# SCH_Clock_Led.net
KiCad netlist of a schematic drawn in Altium Designer
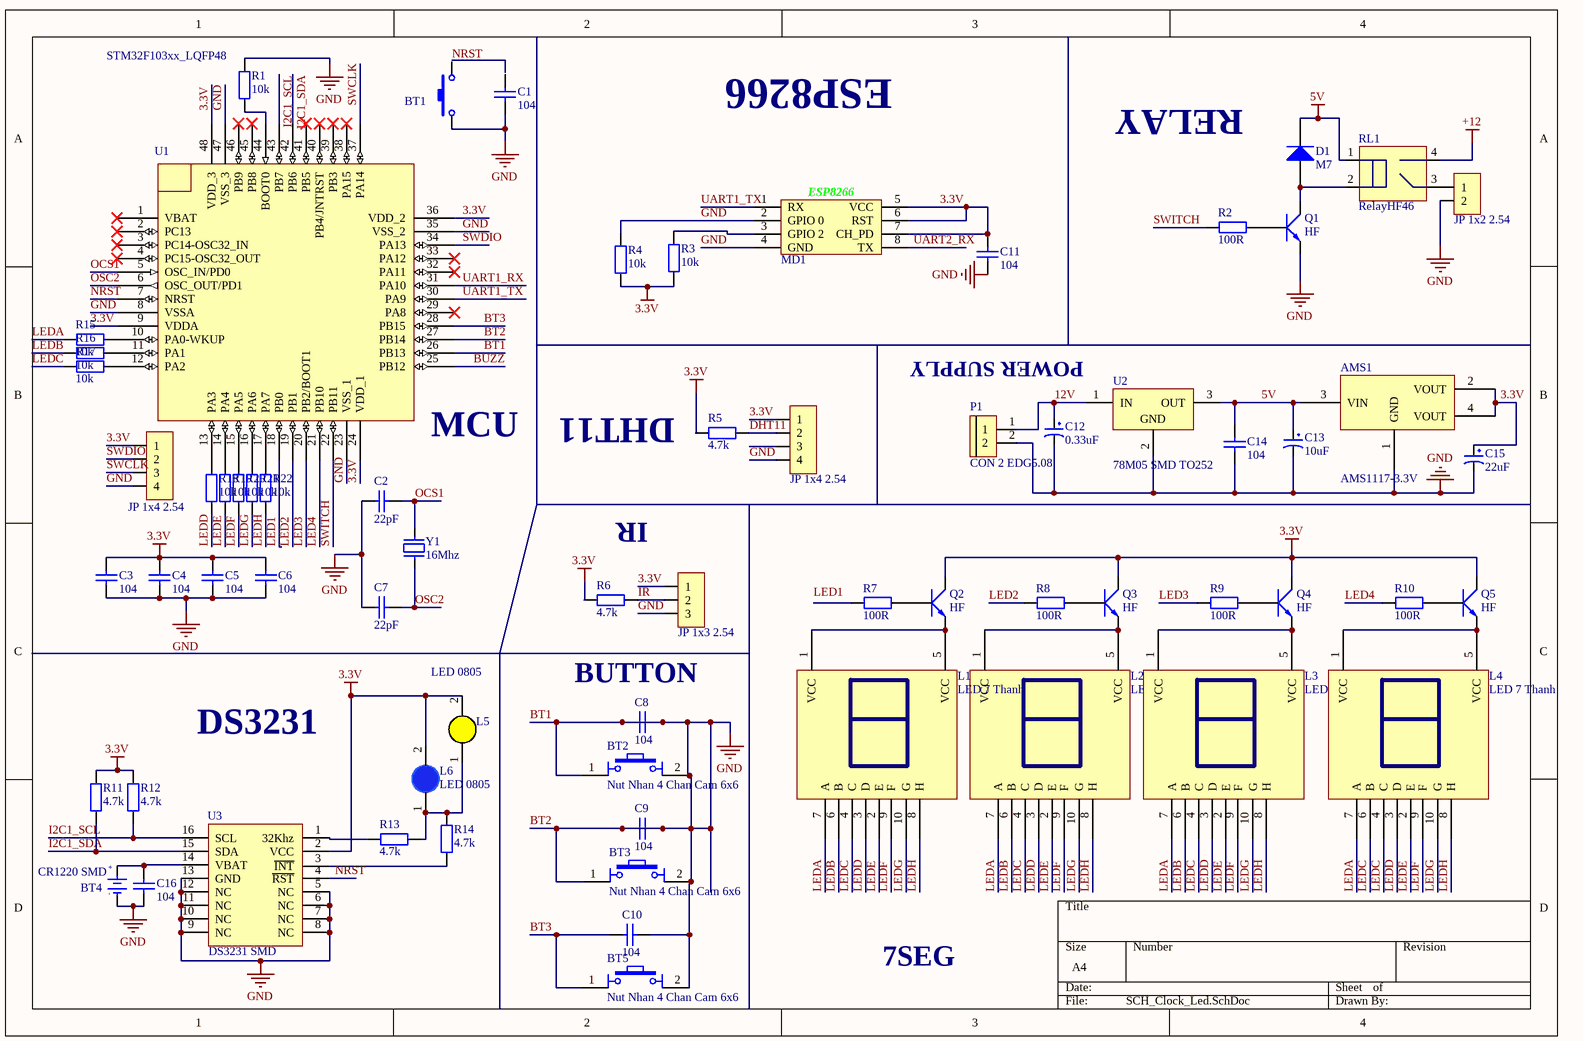
[diagram p0: SCH_Clock_Led.SchDoc]

(export (version "E")
  (design (tool "Eeschema 10.0.6"))
  (components
    (comp (ref "AMS1")
      (value "AMS1117-3.3V")
      (footprint "SOT223")
      (description "Dán")
      (libsource (lib "Altium_Lib_by_KhueNguyenCreator") (part "AMS1117 SMD"))
    )
    (comp (ref "BT1")
      (value "Nut Nhan 2 Chan SMD 3x6x2.5")
      (footprint "Nut Nhan 2 Chan SMD 3x6x2.5")
      (libsource (lib "Altium_Lib_by_KhueNguyenCreator") (part "Nut Nhan 2 Chan SMD 3x6x2.5"))
    )
    (comp (ref "BT2")
      (value "Nut Nhan 4 Chan Cam 6x6")
      (footprint "Nut Nhan 4 Chan Cam 6x6")
      (description "Nut Nhan 4 Chan 6x6mm")
      (libsource (lib "Altium_Lib_by_KhueNguyenCreator") (part "Nut Nhan 4 Chan Cam 6x6"))
    )
    (comp (ref "BT3")
      (value "Nut Nhan 4 Chan Cam 6x6")
      (footprint "Nut Nhan 4 Chan Cam 6x6")
      (description "Nut Nhan 4 Chan 6x6mm")
      (libsource (lib "Altium_Lib_by_KhueNguyenCreator") (part "Nut Nhan 4 Chan Cam 6x6"))
    )
    (comp (ref "BT4")
      (value "CR1220 SMD")
      (footprint "DE PIN CR1220")
      (libsource (lib "Altium_Lib_by_KhueNguyenCreator") (part "De pin CR1220 SMD"))
    )
    (comp (ref "BT5")
      (value "Nut Nhan 4 Chan Cam 6x6")
      (footprint "Nut Nhan 4 Chan Cam 6x6")
      (description "Nut Nhan 4 Chan 6x6mm")
      (libsource (lib "Altium_Lib_by_KhueNguyenCreator") (part "Nut Nhan 4 Chan Cam 6x6"))
    )
    (comp (ref "C1")
      (value "104")
      (footprint "tu 0805")
      (description "Dán")
      (libsource (lib "Altium_Lib_by_KhueNguyenCreator") (part "Tu 0805 104 50V 10%"))
    )
    (comp (ref "C2")
      (value "22pF")
      (footprint "tu 0805")
      (description "Dán")
      (libsource (lib "Altium_Lib_by_KhueNguyenCreator") (part "Tu 0805 22pF 50V 10%"))
    )
    (comp (ref "C3")
      (value "104")
      (footprint "tu 0805")
      (description "Dán")
      (libsource (lib "Altium_Lib_by_KhueNguyenCreator") (part "Tu 0805 104 50V 10%"))
    )
    (comp (ref "C4")
      (value "104")
      (footprint "tu 0805")
      (description "Dán")
      (libsource (lib "Altium_Lib_by_KhueNguyenCreator") (part "Tu 0805 104 50V 10%"))
    )
    (comp (ref "C5")
      (value "104")
      (footprint "tu 0805")
      (description "Dán")
      (libsource (lib "Altium_Lib_by_KhueNguyenCreator") (part "Tu 0805 104 50V 10%"))
    )
    (comp (ref "C6")
      (value "104")
      (footprint "tu 0805")
      (description "Dán")
      (libsource (lib "Altium_Lib_by_KhueNguyenCreator") (part "Tu 0805 104 50V 10%"))
    )
    (comp (ref "C7")
      (value "22pF")
      (footprint "tu 0805")
      (description "Dán")
      (libsource (lib "Altium_Lib_by_KhueNguyenCreator") (part "Tu 0805 22pF 50V 10%"))
    )
    (comp (ref "C8")
      (value "104")
      (footprint "tu 0805")
      (description "Dán")
      (libsource (lib "Altium_Lib_by_KhueNguyenCreator") (part "Tu 0805 104 50V 10%"))
    )
    (comp (ref "C9")
      (value "104")
      (footprint "tu 0805")
      (description "Dán")
      (libsource (lib "Altium_Lib_by_KhueNguyenCreator") (part "Tu 0805 104 50V 10%"))
    )
    (comp (ref "C10")
      (value "104")
      (footprint "tu 0805")
      (description "Dán")
      (libsource (lib "Altium_Lib_by_KhueNguyenCreator") (part "Tu 0805 104 50V 10%"))
    )
    (comp (ref "C11")
      (value "104")
      (footprint "tu 0805")
      (description "Dán")
      (libsource (lib "Altium_Lib_by_KhueNguyenCreator") (part "Tu 0805 104 50V 10%"))
    )
    (comp (ref "C12")
      (value "0.33uF")
      (footprint "tu hoa 5mm")
      (description "Cắm")
      (libsource (lib "Altium_Lib_by_KhueNguyenCreator") (part "Tu Hoa 0.33uF 50V 5x11"))
    )
    (comp (ref "C13")
      (value "10uF")
      (footprint "tu hoa 13mm")
      (description "Cắm")
      (libsource (lib "Altium_Lib_by_KhueNguyenCreator") (part "Tu Hoa 10uF 450V 13x20"))
    )
    (comp (ref "C14")
      (value "104")
      (footprint "tu 0805")
      (description "Dán")
      (libsource (lib "Altium_Lib_by_KhueNguyenCreator") (part "Tu 0805 104 50V 10%"))
    )
    (comp (ref "C15")
      (value "22uF")
      (footprint "tu hoa 5mm")
      (description "Cắm")
      (libsource (lib "Altium_Lib_by_KhueNguyenCreator") (part "Tu Hoa 22uF 35V 5x11"))
    )
    (comp (ref "C16")
      (value "104")
      (footprint "tu 0805")
      (description "Dán")
      (libsource (lib "Altium_Lib_by_KhueNguyenCreator") (part "Tu 0805 104 50V 10%"))
    )
    (comp (ref "D1")
      (value "M7")
      (footprint "DIODE SMA")
      (description "Dán")
      (libsource (lib "Altium_Lib_by_KhueNguyenCreator") (part "Diode M7 ( 4007 )"))
    )
    (comp (ref "JP1")
      (value "JP 1x4 2.54")
      (footprint "JP 1x4 DT")
      (description "Cắm")
      (libsource (lib "Altium_Lib_by_KhueNguyenCreator") (part "JP 1x4 2.54 Duc Thang"))
    )
    (comp (ref "JP2")
      (value "JP 1x4 2.54")
      (footprint "JP 1x4 DT")
      (description "Cắm")
      (libsource (lib "Altium_Lib_by_KhueNguyenCreator") (part "JP 1x4 2.54 Duc Thang"))
    )
    (comp (ref "JP3")
      (value "JP 1x3 2.54")
      (footprint "JP 1x3 CT")
      (description "Cắm")
      (libsource (lib "Altium_Lib_by_KhueNguyenCreator") (part "JP 1x3 2.54 Cai Thang"))
    )
    (comp (ref "JP4")
      (value "JP 1x2 2.54")
      (footprint "JP 1x2 DT")
      (description "Cắm")
      (libsource (lib "Altium_Lib_by_KhueNguyenCreator") (part "JP 1x2 2.54 Duc Thang"))
    )
    (comp (ref "L1")
      (value "LED 7 Thanh")
      (description "Dán")
      (libsource (lib "Altium_Lib_by_KhueNguyenCreator") (part "LED 7x1 2.3inch Anot"))
    )
    (comp (ref "L2")
      (value "LED 7 Thanh")
      (description "Dán")
      (libsource (lib "Altium_Lib_by_KhueNguyenCreator") (part "LED 7x1 2.3inch Anot"))
    )
    (comp (ref "L3")
      (value "LED 7 Thanh")
      (description "Dán")
      (libsource (lib "Altium_Lib_by_KhueNguyenCreator") (part "LED 7x1 2.3inch Anot"))
    )
    (comp (ref "L4")
      (value "LED 7 Thanh")
      (description "Dán")
      (libsource (lib "Altium_Lib_by_KhueNguyenCreator") (part "LED 7x1 2.3inch Anot"))
    )
    (comp (ref "L5")
      (value "LED 0805")
      (footprint "LED-1206-Yellow")
      (description "Dán")
      (libsource (lib "Altium_Lib_by_KhueNguyenCreator") (part "LED 1206 Vang"))
    )
    (comp (ref "L6")
      (value "LED 0805")
      (footprint "LED-0805-Blue")
      (description "Dán")
      (libsource (lib "Altium_Lib_by_KhueNguyenCreator") (part "LED 0805 Xanh Duong"))
    )
    (comp (ref "MD1")
      (value "ESP8266 Module")
      (footprint "ESP2866 Module")
      (libsource (lib "Altium_Lib_by_KhueNguyenCreator") (part "ESP8266 Module"))
    )
    (comp (ref "P1")
      (value "CON 2 EDG5.08")
      (footprint "CON 2 2EDG5.08")
      (description "Cắm")
      (libsource (lib "Altium_Lib_by_KhueNguyenCreator") (part "CON 2 EDG5.08"))
    )
    (comp (ref "Q1")
      (value "HF")
      (footprint "SOT23")
      (description "NPN transistor")
      (libsource (lib "Altium_Lib_by_KhueNguyenCreator") (part "C1815 HF SMD"))
    )
    (comp (ref "Q2")
      (value "HF")
      (footprint "SOT23")
      (description "NPN transistor")
      (libsource (lib "Altium_Lib_by_KhueNguyenCreator") (part "C1815 HF SMD"))
    )
    (comp (ref "Q3")
      (value "HF")
      (footprint "SOT23")
      (description "NPN transistor")
      (libsource (lib "Altium_Lib_by_KhueNguyenCreator") (part "C1815 HF SMD"))
    )
    (comp (ref "Q4")
      (value "HF")
      (footprint "SOT23")
      (description "NPN transistor")
      (libsource (lib "Altium_Lib_by_KhueNguyenCreator") (part "C1815 HF SMD"))
    )
    (comp (ref "Q5")
      (value "HF")
      (footprint "SOT23")
      (description "NPN transistor")
      (libsource (lib "Altium_Lib_by_KhueNguyenCreator") (part "C1815 HF SMD"))
    )
    (comp (ref "R1")
      (value "10k")
      (footprint "tro smd 0805")
      (description "Dán")
      (libsource (lib "Altium_Lib_by_KhueNguyenCreator") (part "Tro 0805 5% 10k"))
    )
    (comp (ref "R2")
      (value "100R")
      (footprint "tro smd 0805")
      (description "Dán")
      (libsource (lib "Altium_Lib_by_KhueNguyenCreator") (part "Tro 0805 5% 100R"))
    )
    (comp (ref "R3")
      (value "10k")
      (footprint "tro smd 0805")
      (description "Dán")
      (libsource (lib "Altium_Lib_by_KhueNguyenCreator") (part "Tro 0805 5% 10k"))
    )
    (comp (ref "R4")
      (value "10k")
      (footprint "tro smd 0805")
      (description "Dán")
      (libsource (lib "Altium_Lib_by_KhueNguyenCreator") (part "Tro 0805 5% 10k"))
    )
    (comp (ref "R5")
      (value "4.7k")
      (footprint "tro smd 0805")
      (description "Dán")
      (libsource (lib "Altium_Lib_by_KhueNguyenCreator") (part "Tro 0805 5% 4.7k"))
    )
    (comp (ref "R6")
      (value "4.7k")
      (footprint "tro smd 0805")
      (description "Dán")
      (libsource (lib "Altium_Lib_by_KhueNguyenCreator") (part "Tro 0805 5% 4.7k"))
    )
    (comp (ref "R7")
      (value "100R")
      (footprint "tro smd 0805")
      (description "Dán")
      (libsource (lib "Altium_Lib_by_KhueNguyenCreator") (part "Tro 0805 5% 100R"))
    )
    (comp (ref "R8")
      (value "100R")
      (footprint "tro smd 0805")
      (description "Dán")
      (libsource (lib "Altium_Lib_by_KhueNguyenCreator") (part "Tro 0805 5% 100R"))
    )
    (comp (ref "R9")
      (value "100R")
      (footprint "tro smd 0805")
      (description "Dán")
      (libsource (lib "Altium_Lib_by_KhueNguyenCreator") (part "Tro 0805 5% 100R"))
    )
    (comp (ref "R10")
      (value "100R")
      (footprint "tro smd 0805")
      (description "Dán")
      (libsource (lib "Altium_Lib_by_KhueNguyenCreator") (part "Tro 0805 5% 100R"))
    )
    (comp (ref "R11")
      (value "4.7k")
      (footprint "tro smd 0805")
      (description "Dán")
      (libsource (lib "Altium_Lib_by_KhueNguyenCreator") (part "Tro 0805 5% 4.7k"))
    )
    (comp (ref "R12")
      (value "4.7k")
      (footprint "tro smd 0805")
      (description "Dán")
      (libsource (lib "Altium_Lib_by_KhueNguyenCreator") (part "Tro 0805 5% 4.7k"))
    )
    (comp (ref "R13")
      (value "4.7k")
      (footprint "tro smd 0805")
      (description "Dán")
      (libsource (lib "Altium_Lib_by_KhueNguyenCreator") (part "Tro 0805 5% 4.7k"))
    )
    (comp (ref "R14")
      (value "4.7k")
      (footprint "tro smd 0805")
      (description "Dán")
      (libsource (lib "Altium_Lib_by_KhueNguyenCreator") (part "Tro 0805 5% 4.7k"))
    )
    (comp (ref "R15")
      (value "10k")
      (footprint "tro smd 0805")
      (description "Dán")
      (libsource (lib "Altium_Lib_by_KhueNguyenCreator") (part "Tro 0805 5% 10k"))
    )
    (comp (ref "R16")
      (value "10k")
      (footprint "tro smd 0805")
      (description "Dán")
      (libsource (lib "Altium_Lib_by_KhueNguyenCreator") (part "Tro 0805 5% 10k"))
    )
    (comp (ref "R17")
      (value "10k")
      (footprint "tro smd 0805")
      (description "Dán")
      (libsource (lib "Altium_Lib_by_KhueNguyenCreator") (part "Tro 0805 5% 10k"))
    )
    (comp (ref "R18")
      (value "10k")
      (footprint "tro smd 0805")
      (description "Dán")
      (libsource (lib "Altium_Lib_by_KhueNguyenCreator") (part "Tro 0805 5% 10k"))
    )
    (comp (ref "R19")
      (value "10k")
      (footprint "tro smd 0805")
      (description "Dán")
      (libsource (lib "Altium_Lib_by_KhueNguyenCreator") (part "Tro 0805 5% 10k"))
    )
    (comp (ref "R20")
      (value "10k")
      (footprint "tro smd 0805")
      (description "Dán")
      (libsource (lib "Altium_Lib_by_KhueNguyenCreator") (part "Tro 0805 5% 10k"))
    )
    (comp (ref "R21")
      (value "10k")
      (footprint "tro smd 0805")
      (description "Dán")
      (libsource (lib "Altium_Lib_by_KhueNguyenCreator") (part "Tro 0805 5% 10k"))
    )
    (comp (ref "R22")
      (value "10k")
      (footprint "tro smd 0805")
      (description "Dán")
      (libsource (lib "Altium_Lib_by_KhueNguyenCreator") (part "Tro 0805 5% 10k"))
    )
    (comp (ref "RL1")
      (value "RelayHF46")
      (footprint "Relay 4 chan HF46F")
      (description "Relay 4 chan HF46F")
      (libsource (lib "Altium_Lib_by_KhueNguyenCreator") (part "Relay 4 chan HF46F"))
    )
    (comp (ref "U1")
      (value "STM32F103xx_LQFP48")
      (footprint "STM32_LQPF48")
      (fields (field (name "PUBLISHER") "Altium Limited"))
      (libsource (lib "Altium_Lib_by_KhueNguyenCreator") (part "STM32F103xx_LQFP48"))
    )
    (comp (ref "U2")
      (value "78M05 SMD TO252")
      (footprint "TO252")
      (description "Dán")
      (libsource (lib "Altium_Lib_by_KhueNguyenCreator") (part "78M05 SMD TO252"))
    )
    (comp (ref "U3")
      (value "DS3231 SMD")
      (footprint "SOIC 16")
      (description "SOIC")
      (libsource (lib "Altium_Lib_by_KhueNguyenCreator") (part "DS3231 SMD"))
    )
    (comp (ref "Y1")
      (value "16Mhz")
      (footprint "Thach Anh 2 chan SMD")
      (description "Crystal For all Crystal 2pin.")
      (libsource (lib "Altium_Lib_by_KhueNguyenCreator") (part "Thach Anh 2 chan SMD"))
    )
  )
  (nets
    (net (code "1") (name "+12") (class "Default")
      (node (ref "RL1") (pin "4") (pinfunction "AC/DC_4") (pintype "passive"))
    )
    (net (code "2") (name "/12V") (class "Default")
      (node (ref "C12") (pin "1") (pinfunction "1_1") (pintype "passive"))
      (node (ref "P1") (pin "1") (pinfunction "1_1") (pintype "passive"))
      (node (ref "U2") (pin "1") (pinfunction "IN_1") (pintype "power_in"))
    )
    (net (code "3") (name "/BT3") (class "Default")
      (node (ref "BT5") (pin "1") (pintype "passive"))
      (node (ref "C10") (pin "2") (pinfunction "2_2") (pintype "passive"))
      (node (ref "U1") (pin "28") (pinfunction "PB15_28") (pintype "bidirectional"))
    )
    (net (code "4") (name "/BUZZ") (class "Default")
      (node (ref "U1") (pin "25") (pinfunction "PB12_25") (pintype "bidirectional"))
    )
    (net (code "5") (name "/DHT11") (class "Default")
      (node (ref "JP1") (pin "2") (pinfunction "2_2") (pintype "passive"))
      (node (ref "R5") (pin "2") (pinfunction "2_2") (pintype "passive"))
    )
    (net (code "6") (name "/I2C1_SCL") (class "Default")
      (node (ref "R12") (pin "1") (pinfunction "1_1") (pintype "passive"))
      (node (ref "U1") (pin "43") (pinfunction "PB7_43") (pintype "bidirectional"))
      (node (ref "U3") (pin "16") (pinfunction "SCL_16") (pintype "power_in"))
    )
    (net (code "7") (name "/I2C1_SDA") (class "Default")
      (node (ref "R11") (pin "1") (pinfunction "1_1") (pintype "passive"))
      (node (ref "U1") (pin "42") (pinfunction "PB6_42") (pintype "bidirectional"))
      (node (ref "U3") (pin "15") (pinfunction "SDA_15") (pintype "power_in"))
    )
    (net (code "8") (name "/IR") (class "Default")
      (node (ref "JP3") (pin "2") (pinfunction "2_2") (pintype "passive"))
      (node (ref "R6") (pin "2") (pinfunction "2_2") (pintype "passive"))
    )
    (net (code "9") (name "/LED1") (class "Default")
      (node (ref "U1") (pin "18") (pinfunction "PB0_18") (pintype "bidirectional"))
    )
    (net (code "10") (name "/LED2") (class "Default")
      (node (ref "R8") (pin "1") (pinfunction "1_1") (pintype "passive"))
      (node (ref "U1") (pin "19") (pinfunction "PB1_19") (pintype "bidirectional"))
    )
    (net (code "11") (name "/LED3") (class "Default")
      (node (ref "R9") (pin "1") (pinfunction "1_1") (pintype "passive"))
      (node (ref "U1") (pin "20") (pinfunction "PB2/BOOT1_20") (pintype "bidirectional"))
    )
    (net (code "12") (name "/LED4") (class "Default")
      (node (ref "R10") (pin "1") (pinfunction "1_1") (pintype "passive"))
      (node (ref "U1") (pin "21") (pinfunction "PB10_21") (pintype "bidirectional"))
    )
    (net (code "13") (name "/LEDA") (class "Default")
      (node (ref "L1") (pin "7") (pinfunction "A_7") (pintype "passive"))
      (node (ref "L2") (pin "7") (pinfunction "A_7") (pintype "passive"))
      (node (ref "L3") (pin "7") (pinfunction "A_7") (pintype "passive"))
      (node (ref "L4") (pin "7") (pinfunction "A_7") (pintype "passive"))
      (node (ref "R15") (pin "1") (pinfunction "1_1") (pintype "passive"))
    )
    (net (code "14") (name "/LEDB") (class "Default")
      (node (ref "L1") (pin "6") (pinfunction "B_6") (pintype "passive"))
      (node (ref "L2") (pin "6") (pinfunction "B_6") (pintype "passive"))
      (node (ref "L3") (pin "6") (pinfunction "B_6") (pintype "passive"))
      (node (ref "R16") (pin "1") (pinfunction "1_1") (pintype "passive"))
    )
    (net (code "15") (name "/LEDC") (class "Default")
      (node (ref "L1") (pin "4") (pinfunction "C_4") (pintype "passive"))
      (node (ref "L2") (pin "4") (pinfunction "C_4") (pintype "passive"))
      (node (ref "L3") (pin "4") (pinfunction "C_4") (pintype "passive"))
      (node (ref "L4") (pin "4") (pinfunction "C_4") (pintype "passive"))
      (node (ref "L4") (pin "6") (pinfunction "B_6") (pintype "passive"))
      (node (ref "R17") (pin "1") (pinfunction "1_1") (pintype "passive"))
    )
    (net (code "16") (name "/LEDD") (class "Default")
      (node (ref "L1") (pin "3") (pinfunction "D_3") (pintype "passive"))
      (node (ref "L2") (pin "3") (pinfunction "D_3") (pintype "passive"))
      (node (ref "L3") (pin "3") (pinfunction "D_3") (pintype "passive"))
      (node (ref "L4") (pin "3") (pinfunction "D_3") (pintype "passive"))
      (node (ref "R18") (pin "1") (pinfunction "1_1") (pintype "passive"))
    )
    (net (code "17") (name "/LEDE") (class "Default")
      (node (ref "L1") (pin "2") (pinfunction "E_2") (pintype "passive"))
      (node (ref "L2") (pin "2") (pinfunction "E_2") (pintype "passive"))
      (node (ref "L3") (pin "2") (pinfunction "E_2") (pintype "passive"))
      (node (ref "L4") (pin "2") (pinfunction "E_2") (pintype "passive"))
      (node (ref "R19") (pin "1") (pinfunction "1_1") (pintype "passive"))
    )
    (net (code "18") (name "/LEDF") (class "Default")
      (node (ref "L1") (pin "9") (pinfunction "F_9") (pintype "passive"))
      (node (ref "L2") (pin "9") (pinfunction "F_9") (pintype "passive"))
      (node (ref "L3") (pin "9") (pinfunction "F_9") (pintype "passive"))
      (node (ref "L4") (pin "9") (pinfunction "F_9") (pintype "passive"))
      (node (ref "R20") (pin "1") (pinfunction "1_1") (pintype "passive"))
    )
    (net (code "19") (name "/LEDG") (class "Default")
      (node (ref "L1") (pin "10") (pinfunction "G_10") (pintype "passive"))
      (node (ref "L2") (pin "10") (pinfunction "G_10") (pintype "passive"))
      (node (ref "L3") (pin "10") (pinfunction "G_10") (pintype "passive"))
      (node (ref "L4") (pin "10") (pinfunction "G_10") (pintype "passive"))
      (node (ref "R21") (pin "1") (pinfunction "1_1") (pintype "passive"))
    )
    (net (code "20") (name "/LEDH") (class "Default")
      (node (ref "L1") (pin "8") (pinfunction "H_8") (pintype "passive"))
      (node (ref "L2") (pin "8") (pinfunction "H_8") (pintype "passive"))
      (node (ref "L3") (pin "8") (pinfunction "H_8") (pintype "passive"))
      (node (ref "L4") (pin "8") (pinfunction "H_8") (pintype "passive"))
      (node (ref "R22") (pin "1") (pinfunction "1_1") (pintype "passive"))
    )
    (net (code "21") (name "/NRST") (class "Default")
      (node (ref "BT1") (pin "2") (pinfunction "2_2") (pintype "passive"))
      (node (ref "U1") (pin "7") (pinfunction "NRST_7") (pintype "bidirectional"))
      (node (ref "U3") (pin "4") (pinfunction "~{RST}_4") (pintype "power_in"))
    )
    (net (code "22") (name "/OCS1") (class "Default")
      (node (ref "C2") (pin "2") (pinfunction "2_2") (pintype "passive"))
      (node (ref "U1") (pin "5") (pinfunction "OSC_IN/PD0_5") (pintype "input"))
      (node (ref "Y1") (pin "2") (pinfunction "2_2") (pintype "passive"))
    )
    (net (code "23") (name "/OSC2") (class "Default")
      (node (ref "C7") (pin "2") (pinfunction "2_2") (pintype "passive"))
      (node (ref "U1") (pin "6") (pinfunction "OSC_OUT/PD1_6") (pintype "output"))
      (node (ref "Y1") (pin "1") (pinfunction "1_1") (pintype "passive"))
    )
    (net (code "24") (name "/SWCLK") (class "Default")
      (node (ref "JP2") (pin "3") (pinfunction "3_3") (pintype "passive"))
      (node (ref "U1") (pin "37") (pinfunction "PA14_37") (pintype "bidirectional"))
    )
    (net (code "25") (name "/SWDIO") (class "Default")
      (node (ref "JP2") (pin "2") (pinfunction "2_2") (pintype "passive"))
      (node (ref "U1") (pin "34") (pinfunction "PA13_34") (pintype "bidirectional"))
    )
    (net (code "26") (name "/SWITCH") (class "Default")
      (node (ref "R2") (pin "1") (pinfunction "1_1") (pintype "passive"))
      (node (ref "U1") (pin "22") (pinfunction "PB11_22") (pintype "bidirectional"))
    )
    (net (code "27") (name "/UART1_RX") (class "Default")
      (node (ref "U1") (pin "31") (pinfunction "PA10_31") (pintype "bidirectional"))
    )
    (net (code "28") (name "/UART1_TX") (class "Default")
      (node (ref "MD1") (pin "1") (pinfunction "RX_1") (pintype "passive"))
      (node (ref "U1") (pin "30") (pinfunction "PA9_30") (pintype "bidirectional"))
    )
    (net (code "29") (name "/UART2_RX") (class "Default")
      (node (ref "MD1") (pin "8") (pinfunction "TX_8") (pintype "passive"))
    )
    (net (code "30") (name "3.3V") (class "Default")
      (node (ref "AMS1") (pin "2") (pinfunction "VOUT_2") (pintype "passive"))
      (node (ref "AMS1") (pin "4") (pinfunction "VOUT_4") (pintype "passive"))
      (node (ref "C11") (pin "2") (pinfunction "2_2") (pintype "passive"))
      (node (ref "C15") (pin "1") (pinfunction "1_1") (pintype "passive"))
      (node (ref "C3") (pin "1") (pinfunction "1_1") (pintype "passive"))
      (node (ref "C4") (pin "1") (pinfunction "1_1") (pintype "passive"))
      (node (ref "C5") (pin "1") (pinfunction "1_1") (pintype "passive"))
      (node (ref "C6") (pin "1") (pinfunction "1_1") (pintype "passive"))
      (node (ref "JP1") (pin "1") (pinfunction "1_1") (pintype "passive"))
      (node (ref "JP2") (pin "1") (pinfunction "1_1") (pintype "passive"))
      (node (ref "JP3") (pin "1") (pinfunction "1_1") (pintype "passive"))
      (node (ref "L5") (pin "2") (pinfunction "K_2") (pintype "passive"))
      (node (ref "L6") (pin "2") (pinfunction "K_2") (pintype "passive"))
      (node (ref "MD1") (pin "5") (pinfunction "VCC_5") (pintype "passive"))
      (node (ref "MD1") (pin "6") (pinfunction "RST_6") (pintype "passive"))
      (node (ref "MD1") (pin "7") (pinfunction "CH_PD_7") (pintype "passive"))
      (node (ref "Q2") (pin "3") (pinfunction "C_3") (pintype "passive"))
      (node (ref "Q3") (pin "3") (pinfunction "C_3") (pintype "passive"))
      (node (ref "Q4") (pin "3") (pinfunction "C_3") (pintype "passive"))
      (node (ref "Q5") (pin "3") (pinfunction "C_3") (pintype "passive"))
      (node (ref "R11") (pin "2") (pinfunction "2_2") (pintype "passive"))
      (node (ref "R12") (pin "2") (pinfunction "2_2") (pintype "passive"))
      (node (ref "R3") (pin "2") (pinfunction "2_2") (pintype "passive"))
      (node (ref "R4") (pin "1") (pinfunction "1_1") (pintype "passive"))
      (node (ref "R5") (pin "1") (pinfunction "1_1") (pintype "passive"))
      (node (ref "R6") (pin "1") (pinfunction "1_1") (pintype "passive"))
      (node (ref "U1") (pin "24") (pinfunction "VDD_1_24") (pintype "power_in"))
      (node (ref "U1") (pin "36") (pinfunction "VDD_2_36") (pintype "power_in"))
      (node (ref "U1") (pin "48") (pinfunction "VDD_3_48") (pintype "power_in"))
      (node (ref "U1") (pin "9") (pinfunction "VDDA_9") (pintype "power_in"))
      (node (ref "U3") (pin "2") (pinfunction "VCC_2") (pintype "power_in"))
    )
    (net (code "31") (name "5V") (class "Default")
      (node (ref "AMS1") (pin "3") (pinfunction "VIN_3") (pintype "passive"))
      (node (ref "C13") (pin "1") (pinfunction "1_1") (pintype "passive"))
      (node (ref "C14") (pin "1") (pinfunction "1_1") (pintype "passive"))
      (node (ref "D1") (pin "2") (pinfunction "K_2") (pintype "passive"))
      (node (ref "RL1") (pin "1") (pintype "passive"))
      (node (ref "U2") (pin "3") (pinfunction "OUT_3") (pintype "power_in"))
    )
    (net (code "32") (name "GND") (class "Default")
      (node (ref "AMS1") (pin "1") (pinfunction "GND_1") (pintype "passive"))
      (node (ref "BT1") (pin "1") (pinfunction "1_1") (pintype "passive"))
      (node (ref "BT2") (pin "1") (pintype "passive"))
      (node (ref "BT2") (pin "2") (pintype "passive"))
      (node (ref "BT3") (pin "1") (pintype "passive"))
      (node (ref "BT3") (pin "2") (pintype "passive"))
      (node (ref "BT4") (pin "2") (pinfunction "GND_2") (pintype "passive"))
      (node (ref "BT5") (pin "2") (pintype "passive"))
      (node (ref "C1") (pin "2") (pinfunction "2_2") (pintype "passive"))
      (node (ref "C10") (pin "1") (pinfunction "1_1") (pintype "passive"))
      (node (ref "C11") (pin "1") (pinfunction "1_1") (pintype "passive"))
      (node (ref "C12") (pin "2") (pinfunction "2_2") (pintype "passive"))
      (node (ref "C13") (pin "2") (pinfunction "2_2") (pintype "passive"))
      (node (ref "C14") (pin "2") (pinfunction "2_2") (pintype "passive"))
      (node (ref "C15") (pin "2") (pinfunction "2_2") (pintype "passive"))
      (node (ref "C16") (pin "2") (pinfunction "2_2") (pintype "passive"))
      (node (ref "C2") (pin "1") (pinfunction "1_1") (pintype "passive"))
      (node (ref "C3") (pin "2") (pinfunction "2_2") (pintype "passive"))
      (node (ref "C4") (pin "2") (pinfunction "2_2") (pintype "passive"))
      (node (ref "C5") (pin "2") (pinfunction "2_2") (pintype "passive"))
      (node (ref "C6") (pin "2") (pinfunction "2_2") (pintype "passive"))
      (node (ref "C7") (pin "1") (pinfunction "1_1") (pintype "passive"))
      (node (ref "C8") (pin "1") (pinfunction "1_1") (pintype "passive"))
      (node (ref "C8") (pin "2") (pinfunction "2_2") (pintype "passive"))
      (node (ref "C9") (pin "1") (pinfunction "1_1") (pintype "passive"))
      (node (ref "C9") (pin "2") (pinfunction "2_2") (pintype "passive"))
      (node (ref "JP1") (pin "4") (pinfunction "4_4") (pintype "passive"))
      (node (ref "JP2") (pin "4") (pinfunction "4_4") (pintype "passive"))
      (node (ref "JP3") (pin "3") (pinfunction "3_3") (pintype "passive"))
      (node (ref "JP4") (pin "2") (pinfunction "2_2") (pintype "passive"))
      (node (ref "MD1") (pin "2") (pinfunction "GPIO_0_2") (pintype "passive"))
      (node (ref "MD1") (pin "4") (pinfunction "GND_4") (pintype "passive"))
      (node (ref "P1") (pin "2") (pinfunction "2_2") (pintype "passive"))
      (node (ref "Q1") (pin "2") (pinfunction "E_2") (pintype "passive"))
      (node (ref "R1") (pin "2") (pinfunction "2_2") (pintype "passive"))
      (node (ref "R4") (pin "2") (pinfunction "2_2") (pintype "passive"))
      (node (ref "U1") (pin "23") (pinfunction "VSS_1_23") (pintype "power_in"))
      (node (ref "U1") (pin "26") (pinfunction "PB13_26") (pintype "bidirectional"))
      (node (ref "U1") (pin "27") (pinfunction "PB14_27") (pintype "bidirectional"))
      (node (ref "U1") (pin "35") (pinfunction "VSS_2_35") (pintype "power_in"))
      (node (ref "U1") (pin "47") (pinfunction "VSS_3_47") (pintype "power_in"))
      (node (ref "U1") (pin "8") (pinfunction "VSSA_8") (pintype "power_in"))
      (node (ref "U2") (pin "2") (pinfunction "GND_2") (pintype "power_in"))
      (node (ref "U3") (pin "10") (pinfunction "NC_10") (pintype "power_in"))
      (node (ref "U3") (pin "11") (pinfunction "NC_11") (pintype "power_in"))
      (node (ref "U3") (pin "12") (pinfunction "NC_12") (pintype "power_in"))
      (node (ref "U3") (pin "13") (pinfunction "GND_13") (pintype "power_in"))
      (node (ref "U3") (pin "5") (pinfunction "NC_5") (pintype "power_in"))
      (node (ref "U3") (pin "6") (pinfunction "NC_6") (pintype "power_in"))
      (node (ref "U3") (pin "7") (pinfunction "NC_7") (pintype "power_in"))
      (node (ref "U3") (pin "8") (pinfunction "NC_8") (pintype "power_in"))
      (node (ref "U3") (pin "9") (pinfunction "NC_9") (pintype "power_in"))
    )
    (net (code "33") (name "Net-(BT4-+3V)") (class "Default")
      (node (ref "BT4") (pin "1") (pinfunction "+3V_1") (pintype "passive"))
      (node (ref "C16") (pin "1") (pinfunction "1_1") (pintype "passive"))
      (node (ref "U3") (pin "14") (pinfunction "VBAT_14") (pintype "power_in"))
    )
    (net (code "34") (name "Net-(D1-A)") (class "Default")
      (node (ref "D1") (pin "1") (pinfunction "A_1") (pintype "passive"))
      (node (ref "Q1") (pin "3") (pinfunction "C_3") (pintype "passive"))
      (node (ref "RL1") (pin "2") (pintype "passive"))
    )
    (net (code "35") (name "Net-(JP4-Pad1)") (class "Default")
      (node (ref "JP4") (pin "1") (pinfunction "1_1") (pintype "passive"))
      (node (ref "RL1") (pin "3") (pinfunction "AC/DC_3") (pintype "passive"))
    )
    (net (code "36") (name "Net-(L5-A)") (class "Default")
      (node (ref "L5") (pin "1") (pinfunction "A_1") (pintype "passive"))
      (node (ref "L6") (pin "1") (pinfunction "A_1") (pintype "passive"))
      (node (ref "R13") (pin "1") (pinfunction "1_1") (pintype "passive"))
      (node (ref "R14") (pin "1") (pinfunction "1_1") (pintype "passive"))
    )
    (net (code "37") (name "Net-(MD1-GPIO_2)") (class "Default")
      (node (ref "MD1") (pin "3") (pinfunction "GPIO_2_3") (pintype "passive"))
      (node (ref "R3") (pin "1") (pinfunction "1_1") (pintype "passive"))
    )
    (net (code "38") (name "Net-(Q1-B)") (class "Default")
      (node (ref "Q1") (pin "1") (pinfunction "B_1") (pintype "passive"))
      (node (ref "R2") (pin "2") (pinfunction "2_2") (pintype "passive"))
    )
    (net (code "39") (name "Net-(Q2-B)") (class "Default")
      (node (ref "Q2") (pin "1") (pinfunction "B_1") (pintype "passive"))
      (node (ref "R7") (pin "2") (pinfunction "2_2") (pintype "passive"))
    )
    (net (code "40") (name "Net-(Q2-E)") (class "Default")
      (node (ref "L1") (pin "1") (pinfunction "VCC_1") (pintype "passive"))
      (node (ref "L1") (pin "5") (pinfunction "VCC_5") (pintype "passive"))
      (node (ref "Q2") (pin "2") (pinfunction "E_2") (pintype "passive"))
    )
    (net (code "41") (name "Net-(Q3-B)") (class "Default")
      (node (ref "Q3") (pin "1") (pinfunction "B_1") (pintype "passive"))
      (node (ref "R8") (pin "2") (pinfunction "2_2") (pintype "passive"))
    )
    (net (code "42") (name "Net-(Q3-E)") (class "Default")
      (node (ref "L2") (pin "1") (pinfunction "VCC_1") (pintype "passive"))
      (node (ref "L2") (pin "5") (pinfunction "VCC_5") (pintype "passive"))
      (node (ref "Q3") (pin "2") (pinfunction "E_2") (pintype "passive"))
    )
    (net (code "43") (name "Net-(Q4-B)") (class "Default")
      (node (ref "Q4") (pin "1") (pinfunction "B_1") (pintype "passive"))
      (node (ref "R9") (pin "2") (pinfunction "2_2") (pintype "passive"))
    )
    (net (code "44") (name "Net-(Q4-E)") (class "Default")
      (node (ref "L3") (pin "1") (pinfunction "VCC_1") (pintype "passive"))
      (node (ref "L3") (pin "5") (pinfunction "VCC_5") (pintype "passive"))
      (node (ref "Q4") (pin "2") (pinfunction "E_2") (pintype "passive"))
    )
    (net (code "45") (name "Net-(Q5-B)") (class "Default")
      (node (ref "Q5") (pin "1") (pinfunction "B_1") (pintype "passive"))
      (node (ref "R10") (pin "2") (pinfunction "2_2") (pintype "passive"))
    )
    (net (code "46") (name "Net-(Q5-E)") (class "Default")
      (node (ref "L4") (pin "1") (pinfunction "VCC_1") (pintype "passive"))
      (node (ref "L4") (pin "5") (pinfunction "VCC_5") (pintype "passive"))
      (node (ref "Q5") (pin "2") (pinfunction "E_2") (pintype "passive"))
    )
    (net (code "47") (name "Net-(U1-BOOT0)") (class "Default")
      (node (ref "R1") (pin "1") (pinfunction "1_1") (pintype "passive"))
      (node (ref "U1") (pin "44") (pinfunction "BOOT0_44") (pintype "input"))
    )
    (net (code "48") (name "Net-(U1-PA0-WKUP)") (class "Default")
      (node (ref "R15") (pin "2") (pinfunction "2_2") (pintype "passive"))
      (node (ref "U1") (pin "10") (pinfunction "PA0-WKUP_10") (pintype "bidirectional"))
    )
    (net (code "49") (name "Net-(U1-PA1)") (class "Default")
      (node (ref "R16") (pin "2") (pinfunction "2_2") (pintype "passive"))
      (node (ref "U1") (pin "11") (pinfunction "PA1_11") (pintype "bidirectional"))
    )
    (net (code "50") (name "Net-(U1-PA2)") (class "Default")
      (node (ref "R17") (pin "2") (pinfunction "2_2") (pintype "passive"))
      (node (ref "U1") (pin "12") (pinfunction "PA2_12") (pintype "bidirectional"))
    )
    (net (code "51") (name "Net-(U1-PA3)") (class "Default")
      (node (ref "R18") (pin "2") (pinfunction "2_2") (pintype "passive"))
      (node (ref "U1") (pin "13") (pinfunction "PA3_13") (pintype "bidirectional"))
    )
    (net (code "52") (name "Net-(U1-PA4)") (class "Default")
      (node (ref "R19") (pin "2") (pinfunction "2_2") (pintype "passive"))
      (node (ref "U1") (pin "14") (pinfunction "PA4_14") (pintype "bidirectional"))
    )
    (net (code "53") (name "Net-(U1-PA5)") (class "Default")
      (node (ref "R20") (pin "2") (pinfunction "2_2") (pintype "passive"))
      (node (ref "U1") (pin "15") (pinfunction "PA5_15") (pintype "bidirectional"))
    )
    (net (code "54") (name "Net-(U1-PA6)") (class "Default")
      (node (ref "R21") (pin "2") (pinfunction "2_2") (pintype "passive"))
      (node (ref "U1") (pin "16") (pinfunction "PA6_16") (pintype "bidirectional"))
    )
    (net (code "55") (name "Net-(U1-PA7)") (class "Default")
      (node (ref "R22") (pin "2") (pinfunction "2_2") (pintype "passive"))
      (node (ref "U1") (pin "17") (pinfunction "PA7_17") (pintype "bidirectional"))
    )
    (net (code "56") (name "Net-(U3-32Khz)") (class "Default")
      (node (ref "R13") (pin "2") (pinfunction "2_2") (pintype "passive"))
      (node (ref "U3") (pin "1") (pinfunction "32Khz_1") (pintype "power_in"))
    )
    (net (code "57") (name "Net-(U3-~{INT})") (class "Default")
      (node (ref "R14") (pin "2") (pinfunction "2_2") (pintype "passive"))
      (node (ref "U3") (pin "3") (pinfunction "~{INT}_3") (pintype "power_in"))
    )
    (net (code "58") (name "unconnected-(C1-Pad1)") (class "Default")
      (node (ref "C1") (pin "1") (pinfunction "1_1") (pintype "passive"))
    )
    (net (code "59") (name "unconnected-(JP1-Pad3)") (class "Default")
      (node (ref "JP1") (pin "3") (pinfunction "3_3") (pintype "passive"))
    )
    (net (code "60") (name "unconnected-(R7-Pad1)") (class "Default")
      (node (ref "R7") (pin "1") (pinfunction "1_1") (pintype "passive"))
    )
    (net (code "61") (name "unconnected-(U1-PA8-Pad29)") (class "Default")
      (node (ref "U1") (pin "29") (pinfunction "PA8_29") (pintype "bidirectional+no_connect"))
    )
    (net (code "62") (name "unconnected-(U1-PA11-Pad32)") (class "Default")
      (node (ref "U1") (pin "32") (pinfunction "PA11_32") (pintype "bidirectional+no_connect"))
    )
    (net (code "63") (name "unconnected-(U1-PA12-Pad33)") (class "Default")
      (node (ref "U1") (pin "33") (pinfunction "PA12_33") (pintype "bidirectional+no_connect"))
    )
    (net (code "64") (name "unconnected-(U1-PA15-Pad38)") (class "Default")
      (node (ref "U1") (pin "38") (pinfunction "PA15_38") (pintype "bidirectional+no_connect"))
    )
    (net (code "65") (name "unconnected-(U1-PB3-Pad39)") (class "Default")
      (node (ref "U1") (pin "39") (pinfunction "PB3_39") (pintype "bidirectional+no_connect"))
    )
    (net (code "66") (name "unconnected-(U1-PB4{slash}JNTRST-Pad40)") (class "Default")
      (node (ref "U1") (pin "40") (pinfunction "PB4/JNTRST_40") (pintype "bidirectional+no_connect"))
    )
    (net (code "67") (name "unconnected-(U1-PB5-Pad41)") (class "Default")
      (node (ref "U1") (pin "41") (pinfunction "PB5_41") (pintype "bidirectional+no_connect"))
    )
    (net (code "68") (name "unconnected-(U1-PB8-Pad45)") (class "Default")
      (node (ref "U1") (pin "45") (pinfunction "PB8_45") (pintype "bidirectional+no_connect"))
    )
    (net (code "69") (name "unconnected-(U1-PB9-Pad46)") (class "Default")
      (node (ref "U1") (pin "46") (pinfunction "PB9_46") (pintype "bidirectional+no_connect"))
    )
    (net (code "70") (name "unconnected-(U1-PC13-Pad2)") (class "Default")
      (node (ref "U1") (pin "2") (pinfunction "PC13_2") (pintype "bidirectional+no_connect"))
    )
    (net (code "71") (name "unconnected-(U1-PC14-OSC32_IN-Pad3)") (class "Default")
      (node (ref "U1") (pin "3") (pinfunction "PC14-OSC32_IN_3") (pintype "bidirectional+no_connect"))
    )
    (net (code "72") (name "unconnected-(U1-PC15-OSC32_OUT-Pad4)") (class "Default")
      (node (ref "U1") (pin "4") (pinfunction "PC15-OSC32_OUT_4") (pintype "bidirectional+no_connect"))
    )
    (net (code "73") (name "unconnected-(U1-VBAT-Pad1)") (class "Default")
      (node (ref "U1") (pin "1") (pinfunction "VBAT_1") (pintype "power_in+no_connect"))
    )
  )
)
